# 02_CPU.net
KiCad netlist of a schematic drawn in Altium Designer
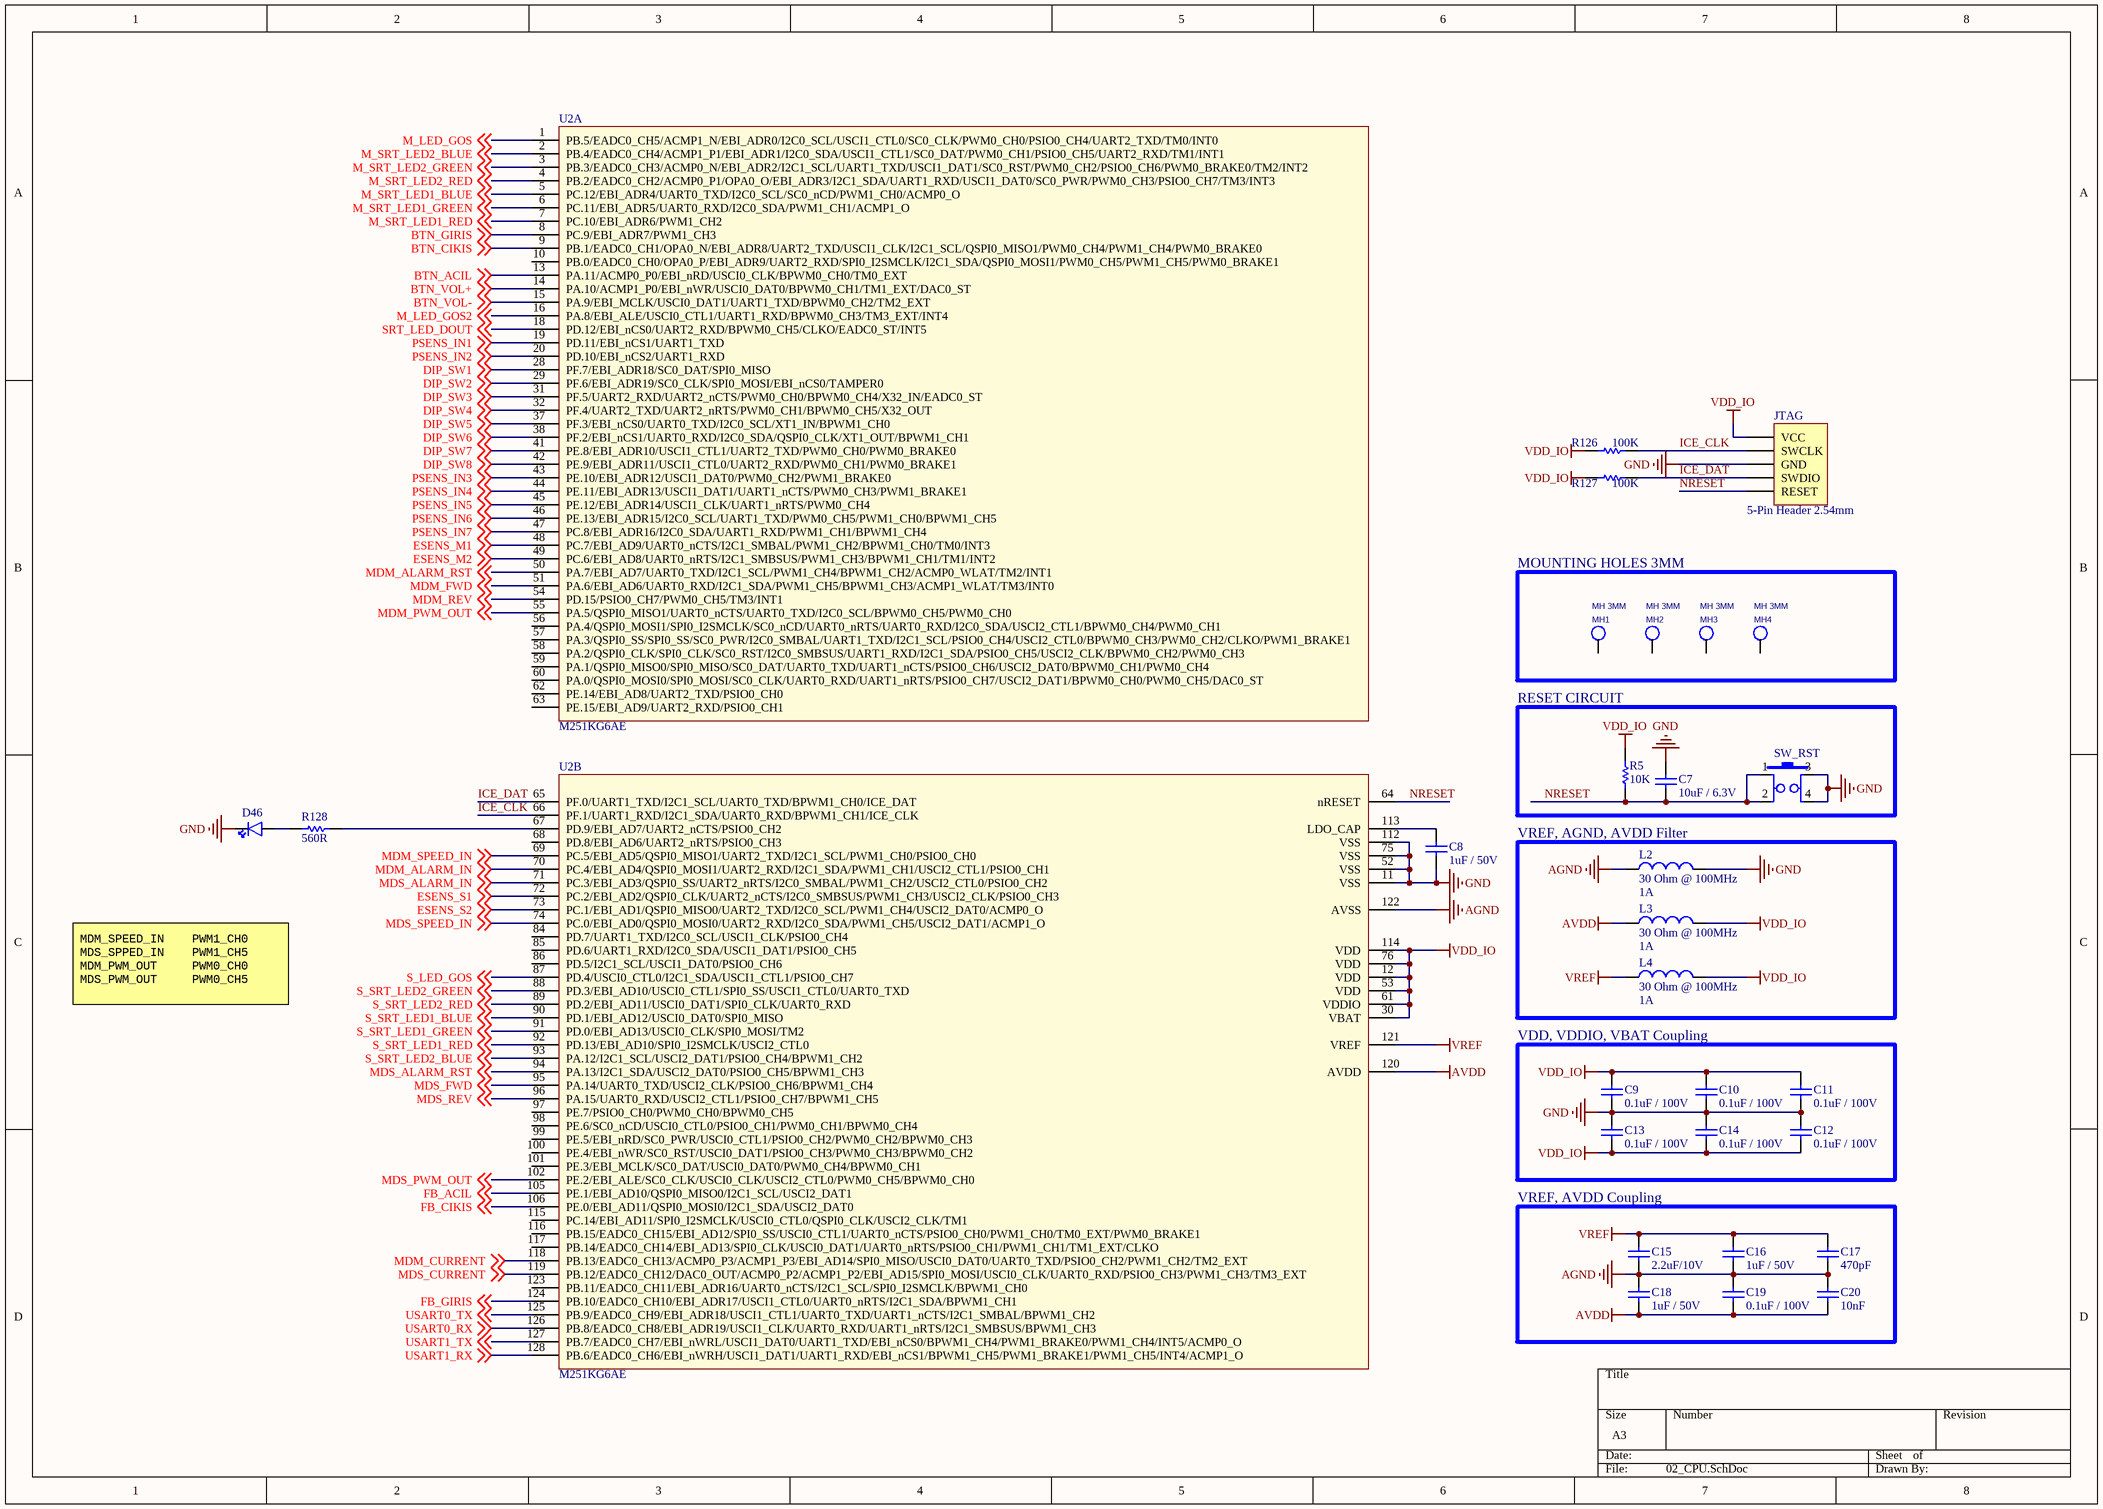
[diagram p0: 02_CPU.SchDoc]

(export (version "E")
  (design (tool "Eeschema 10.0.6"))
  (components
    (comp (ref "C7")
      (value "10uF / 6.3V")
      (footprint "603C")
      (description "10µF ±20% 6.3V Ceramic Capacitor X5R 0603 (1608 Metric)")
      (fields
        (field (name "DIGI-KEY PART NUMBER") "1276-1119-1-ND")
        (field (name "MANUFACTURER") "Samsung Electro-Mechanics")
      )
      (libsource (lib "FKDZ_Altium_Lib") (part "CAP_CER 10UF 6.3V X5R 0603"))
    )
    (comp (ref "C8")
      (value "1uF / 50V")
      (footprint "603C")
      (description "1µF ±10% 50V Ceramic Capacitor X5R 0603 (1608 Metric)")
      (fields
        (field (name "DIGI-KEY PART NUMBER") "1276-1860-2-ND")
        (field (name "MANUFACTURER") "Samsung Electro-Mechanics")
      )
      (libsource (lib "FKDZ_Altium_Lib") (part "CAP CER 1UF 50V X5R 0603"))
    )
    (comp (ref "C9")
      (value "0.1uF / 100V")
      (footprint "603C")
      (description "0.1 µF ±10% 100V Ceramic Capacitor X7R 0603 (1608 Metric)")
      (fields
        (field (name "DIGI-KEY PART NUMBER") "2679-C0603X7R101-104KNPTR-ND")
        (field (name "MANUFACTURER") "Venkel")
      )
      (libsource (lib "FKDZ_Altium_Lib") (part "CAP CER 0.1UF 100V X7R 0603"))
    )
    (comp (ref "C10")
      (value "0.1uF / 100V")
      (footprint "603C")
      (description "0.1 µF ±10% 100V Ceramic Capacitor X7R 0603 (1608 Metric)")
      (fields
        (field (name "DIGI-KEY PART NUMBER") "2679-C0603X7R101-104KNPTR-ND")
        (field (name "MANUFACTURER") "Venkel")
      )
      (libsource (lib "FKDZ_Altium_Lib") (part "CAP CER 0.1UF 100V X7R 0603"))
    )
    (comp (ref "C11")
      (value "0.1uF / 100V")
      (footprint "603C")
      (description "0.1 µF ±10% 100V Ceramic Capacitor X7R 0603 (1608 Metric)")
      (fields
        (field (name "DIGI-KEY PART NUMBER") "2679-C0603X7R101-104KNPTR-ND")
        (field (name "MANUFACTURER") "Venkel")
      )
      (libsource (lib "FKDZ_Altium_Lib") (part "CAP CER 0.1UF 100V X7R 0603"))
    )
    (comp (ref "C12")
      (value "0.1uF / 100V")
      (footprint "603C")
      (description "0.1 µF ±10% 100V Ceramic Capacitor X7R 0603 (1608 Metric)")
      (fields
        (field (name "DIGI-KEY PART NUMBER") "2679-C0603X7R101-104KNPTR-ND")
        (field (name "MANUFACTURER") "Venkel")
      )
      (libsource (lib "FKDZ_Altium_Lib") (part "CAP CER 0.1UF 100V X7R 0603"))
    )
    (comp (ref "C13")
      (value "0.1uF / 100V")
      (footprint "603C")
      (description "0.1 µF ±10% 100V Ceramic Capacitor X7R 0603 (1608 Metric)")
      (fields
        (field (name "DIGI-KEY PART NUMBER") "2679-C0603X7R101-104KNPTR-ND")
        (field (name "MANUFACTURER") "Venkel")
      )
      (libsource (lib "FKDZ_Altium_Lib") (part "CAP CER 0.1UF 100V X7R 0603"))
    )
    (comp (ref "C14")
      (value "0.1uF / 100V")
      (footprint "603C")
      (description "0.1 µF ±10% 100V Ceramic Capacitor X7R 0603 (1608 Metric)")
      (fields
        (field (name "DIGI-KEY PART NUMBER") "2679-C0603X7R101-104KNPTR-ND")
        (field (name "MANUFACTURER") "Venkel")
      )
      (libsource (lib "FKDZ_Altium_Lib") (part "CAP CER 0.1UF 100V X7R 0603"))
    )
    (comp (ref "C15")
      (value "2.2uF/10V")
      (footprint "603C")
      (description "2.2 µF ±10% 10V Ceramic Capacitor X5R 0603 (1608 Metric)")
      (fields
        (field (name "DIGI-KEY PART NUMBER") "2571-GMC10X5R225K10NTTR-ND")
        (field (name "MANUFACTURER") "CAL-CHIP ELECTRONICS, INC.")
      )
      (libsource (lib "FKDZ_Altium_Lib") (part "CAP CER 2.2UF 10V X5R 0603"))
    )
    (comp (ref "C16")
      (value "1uF / 50V")
      (footprint "603C")
      (description "1µF ±10% 50V Ceramic Capacitor X5R 0603 (1608 Metric)")
      (fields
        (field (name "DIGI-KEY PART NUMBER") "1276-1860-2-ND")
        (field (name "MANUFACTURER") "Samsung Electro-Mechanics")
      )
      (libsource (lib "FKDZ_Altium_Lib") (part "CAP CER 1UF 50V X5R 0603"))
    )
    (comp (ref "C17")
      (value "470pF")
      (footprint "603C")
      (description "470pF ±5% 50V Ceramic Capacitor C0G, NP0 0603 (1608 Metric)")
      (fields
        (field (name "DIGI-KEY PART NUMBER") "1276-1168-2-ND")
        (field (name "MANUFACTURER") "Samsung Electro-Mechanics America, Inc.")
      )
      (libsource (lib "FKDZ_Altium_Lib") (part "CAP_CER_470pF_50V_%5_C0G_NP0_ 0603"))
    )
    (comp (ref "C18")
      (value "1uF / 50V")
      (footprint "603C")
      (description "1µF ±10% 50V Ceramic Capacitor X5R 0603 (1608 Metric)")
      (fields
        (field (name "DIGI-KEY PART NUMBER") "1276-1860-2-ND")
        (field (name "MANUFACTURER") "Samsung Electro-Mechanics")
      )
      (libsource (lib "FKDZ_Altium_Lib") (part "CAP CER 1UF 50V X5R 0603"))
    )
    (comp (ref "C19")
      (value "0.1uF / 100V")
      (footprint "603C")
      (description "0.1 µF ±10% 100V Ceramic Capacitor X7R 0603 (1608 Metric)")
      (fields
        (field (name "DIGI-KEY PART NUMBER") "2679-C0603X7R101-104KNPTR-ND")
        (field (name "MANUFACTURER") "Venkel")
      )
      (libsource (lib "FKDZ_Altium_Lib") (part "CAP CER 0.1UF 100V X7R 0603"))
    )
    (comp (ref "C20")
      (value "10nF")
      (footprint "603C")
      (description "10nF ±5% 50V Ceramic Capacitor X7R 0603 (1608 Metric)")
      (fields (field (name "DIGI-KEY PART NUMBER") "311-1778-2-ND") (field (name "MANUFACTURER") "Yageo"))
      (libsource (lib "FKDZ_Altium_Lib") (part "CAP_CER_10nF_50V_%5_ X7R_ 0603"))
    )
    (comp (ref "D46")
      (value "led_green")
      (footprint "805LED")
      (description "LED 2X1.2MM 570NM GN WTR CLR SMD")
      (fields (field (name "DIGI-KEY PART NUMBER") "754-1127-1-ND"))
      (libsource (lib "FKDZ_Altium_Lib") (part "LED_GREEN_0805"))
    )
    (comp (ref "JTAG")
      (value "5-Pin Header 2.54mm")
      (footprint "HDR1X5")
      (description "STM JTAG Header, 5-Pin")
      (libsource (lib "FKDZ_Altium_Lib") (part "STM_JTAG"))
    )
    (comp (ref "L2")
      (value "30 Ohm @ 100MHz")
      (footprint "603L")
      (description "30 Ohms @ 100 MHz 1 Power Line Ferrite Bead 0603 (1608 Metric) 1A 50mOhm")
      (fields
        (field (name "DIGI-KEY PART NUMBER") "490-1035-1-ND")
        (field (name "MANUFACTURER") "Murata Electronics")
        (field (name "IMPEDANCE AT FREQUENCY") "30 Ohm @ 100MHz")
        (field (name "CURRENT RATING (MAX)") "1A")
      )
      (libsource (lib "FKDZ_Altium_Lib") (part "FERRITE BEAD 30 OHM 0603 1LN"))
    )
    (comp (ref "L3")
      (value "30 Ohm @ 100MHz")
      (footprint "603L")
      (description "30 Ohms @ 100 MHz 1 Power Line Ferrite Bead 0603 (1608 Metric) 1A 50mOhm")
      (fields
        (field (name "DIGI-KEY PART NUMBER") "490-1035-1-ND")
        (field (name "MANUFACTURER") "Murata Electronics")
        (field (name "IMPEDANCE AT FREQUENCY") "30 Ohm @ 100MHz")
        (field (name "CURRENT RATING (MAX)") "1A")
      )
      (libsource (lib "FKDZ_Altium_Lib") (part "FERRITE BEAD 30 OHM 0603 1LN"))
    )
    (comp (ref "L4")
      (value "30 Ohm @ 100MHz")
      (footprint "603L")
      (description "30 Ohms @ 100 MHz 1 Power Line Ferrite Bead 0603 (1608 Metric) 1A 50mOhm")
      (fields
        (field (name "DIGI-KEY PART NUMBER") "490-1035-1-ND")
        (field (name "MANUFACTURER") "Murata Electronics")
        (field (name "IMPEDANCE AT FREQUENCY") "30 Ohm @ 100MHz")
        (field (name "CURRENT RATING (MAX)") "1A")
      )
      (libsource (lib "FKDZ_Altium_Lib") (part "FERRITE BEAD 30 OHM 0603 1LN"))
    )
    (comp (ref "MH1")
      (value "MH 3MM")
      (footprint "MH 3.0MM HOLE 5MM PAD")
      (description "Mountin hole, NPTH Drill 3mm")
      (libsource (lib "FKDZ_Altium_Lib") (part "MH 3MMHOLE_5MMPAD"))
    )
    (comp (ref "MH2")
      (value "MH 3MM")
      (footprint "MH 3.0MM HOLE 5MM PAD")
      (description "Mountin hole, NPTH Drill 3mm")
      (libsource (lib "FKDZ_Altium_Lib") (part "MH 3MMHOLE_5MMPAD"))
    )
    (comp (ref "MH3")
      (value "MH 3MM")
      (footprint "MH 3.0MM HOLE 5MM PAD")
      (description "Mountin hole, NPTH Drill 3mm")
      (libsource (lib "FKDZ_Altium_Lib") (part "MH 3MMHOLE_5MMPAD"))
    )
    (comp (ref "MH4")
      (value "MH 3MM")
      (footprint "MH 3.0MM HOLE 5MM PAD")
      (description "Mountin hole, NPTH Drill 3mm")
      (libsource (lib "FKDZ_Altium_Lib") (part "MH 3MMHOLE_5MMPAD"))
    )
    (comp (ref "R5")
      (value "10K")
      (footprint "603R")
      (description "10 kOhms ±5% 0.1W, 1/10W Chip Resistor 0603 (1608 Metric) Moisture Resistant Thick Film")
      (fields (field (name "DIGI-KEY PART NUMBER") "311-10KGRTR-ND") (field (name "MANUFACTURER") "Yageo"))
      (libsource (lib "FKDZ_Altium_Lib") (part "RES_10K_OHM_%5_0.1W_0603"))
    )
    (comp (ref "R126")
      (value "100K")
      (footprint "603R")
      (description "100 kOhms ±1% 0.1W, 1/10W Chip Resistor 0603 (1608 Metric)  Thick Film")
      (fields
        (field (name "DIGI-KEY PART NUMBER") "A106046TR-ND")
        (field (name "MANUFACTURER") "TE Connectivity Passive Product")
      )
      (libsource (lib "FKDZ_Altium_Lib") (part "RES_100K OHM 1% 1/10W 0603"))
    )
    (comp (ref "R127")
      (value "100K")
      (footprint "603R")
      (description "100 kOhms ±1% 0.1W, 1/10W Chip Resistor 0603 (1608 Metric)  Thick Film")
      (fields
        (field (name "DIGI-KEY PART NUMBER") "A106046TR-ND")
        (field (name "MANUFACTURER") "TE Connectivity Passive Product")
      )
      (libsource (lib "FKDZ_Altium_Lib") (part "RES_100K OHM 1% 1/10W 0603"))
    )
    (comp (ref "R128")
      (value "560R")
      (footprint "603R")
      (description "560 Ohms ±5% 0.1W, 1/10W Chip Resistor 0603 (1608 Metric) Moisture Resistant Thick Film")
      (fields (field (name "DIGI-KEY PART NUMBER") "311-560GRCT-ND") (field (name "MANUFACTURER") "Yageo"))
      (libsource (lib "FKDZ_Altium_Lib") (part "RES_560_OHM_%5_0.1W_0603"))
    )
    (comp (ref "SW_RST")
      (value "switch tactile")
      (footprint "SW_TACTILE_6X6mm SMT")
      (description "Tactile Switch SPST-NO Top Actuated Surface Mount")
      (fields (field (name "DIGI-KEY PART NUMBER") "CKN9112TR-ND"))
      (libsource (lib "FKDZ_Altium_Lib") (part "SW_TACTILE_6x6x4.3mm SMT"))
    )
    (comp (ref "U2")
      (value "M251KG6AE")
      (footprint "TSQFP40P1600X1600X160-128N")
      (description "ARM® Cortex®-M23 series Microcontroller IC 32-Bit 48MHz 256KB (256K x 8) FLASH 128-LQFP (14x14)")
      (fields
        (field (name "DIGI-KEY PART NUMBER") "https://www.ozdisan.com/integrated-circuits-ics/embedded-ics/microcontrollers/M251KG6AE")
      )
      (libsource (lib "") (part "IC MCU 32BIT 256KB FLASH 32KB RAM 128LQFP M251KG6AE_1"))
    )
  )
  (nets
    (net (code "1") (name "/ICE_CLK") (class "Default")
      (node (ref "JTAG") (pin "2") (pinfunction "SWCLK_2") (pintype "passive"))
      (node (ref "R126") (pin "2") (pinfunction "2_2") (pintype "passive"))
      (node (ref "U2") (pin "66") (pinfunction "PF.1/UART1_RXD/I2C1_SDA/UART0_RXD/BPWM1_CH1/ICE_CLK_66") (pintype "passive"))
    )
    (net (code "2") (name "/ICE_DAT") (class "Default")
      (node (ref "JTAG") (pin "4") (pinfunction "SWDIO_4") (pintype "passive"))
      (node (ref "R127") (pin "2") (pinfunction "2_2") (pintype "passive"))
      (node (ref "U2") (pin "65") (pinfunction "PF.0/UART1_TXD/I2C1_SCL/UART0_TXD/BPWM1_CH0/ICE_DAT_65") (pintype "passive"))
    )
    (net (code "3") (name "/NRESET") (class "Default")
      (node (ref "C7") (pin "2") (pinfunction "2_2") (pintype "passive"))
      (node (ref "JTAG") (pin "5") (pinfunction "RESET_5") (pintype "passive"))
      (node (ref "R5") (pin "1") (pinfunction "1_1") (pintype "passive"))
      (node (ref "SW_RST") (pin "1") (pinfunction "1_1") (pintype "passive"))
      (node (ref "SW_RST") (pin "2") (pinfunction "2_2") (pintype "passive"))
      (node (ref "U2") (pin "64") (pinfunction "nRESET_64") (pintype "passive"))
    )
    (net (code "4") (name "AGND") (class "Default")
      (node (ref "C15") (pin "1") (pinfunction "1_1") (pintype "passive"))
      (node (ref "C16") (pin "1") (pinfunction "1_1") (pintype "passive"))
      (node (ref "C17") (pin "1") (pinfunction "1_1") (pintype "passive"))
      (node (ref "C18") (pin "2") (pinfunction "2_2") (pintype "passive"))
      (node (ref "C19") (pin "2") (pinfunction "2_2") (pintype "passive"))
      (node (ref "C20") (pin "2") (pinfunction "2_2") (pintype "passive"))
      (node (ref "L2") (pin "1") (pinfunction "1_1") (pintype "passive"))
      (node (ref "U2") (pin "122") (pinfunction "AVSS_122") (pintype "passive"))
    )
    (net (code "5") (name "AVDD") (class "Default")
      (node (ref "C18") (pin "1") (pinfunction "1_1") (pintype "passive"))
      (node (ref "C19") (pin "1") (pinfunction "1_1") (pintype "passive"))
      (node (ref "C20") (pin "1") (pinfunction "1_1") (pintype "passive"))
      (node (ref "L3") (pin "1") (pinfunction "1_1") (pintype "passive"))
      (node (ref "U2") (pin "120") (pinfunction "AVDD_120") (pintype "passive"))
    )
    (net (code "6") (name "BTN_ACIL") (class "Default")
      (node (ref "U2") (pin "13") (pinfunction "PA.11/ACMP0_P0/EBI_nRD/USCI0_CLK/BPWM0_CH0/TM0_EXT_13") (pintype "passive"))
    )
    (net (code "7") (name "BTN_CIKIS") (class "Default")
      (node (ref "U2") (pin "9") (pinfunction "PB.1/EADC0_CH1/OPA0_N/EBI_ADR8/UART2_TXD/USCI1_CLK/I2C1_SCL/QSPI0_MISO1/PWM0_CH4/PWM1_CH4/PWM0_BRAKE0_9") (pintype "passive"))
    )
    (net (code "8") (name "BTN_GIRIS") (class "Default")
      (node (ref "U2") (pin "8") (pinfunction "PC.9/EBI_ADR7/PWM1_CH3_8") (pintype "passive"))
    )
    (net (code "9") (name "BTN_VOL+") (class "Default")
      (node (ref "U2") (pin "14") (pinfunction "PA.10/ACMP1_P0/EBI_nWR/USCI0_DAT0/BPWM0_CH1/TM1_EXT/DAC0_ST_14") (pintype "passive"))
    )
    (net (code "10") (name "BTN_VOL-") (class "Default")
      (node (ref "U2") (pin "15") (pinfunction "PA.9/EBI_MCLK/USCI0_DAT1/UART1_TXD/BPWM0_CH2/TM2_EXT_15") (pintype "passive"))
    )
    (net (code "11") (name "DIP_SW1") (class "Default")
      (node (ref "U2") (pin "28") (pinfunction "PF.7/EBI_ADR18/SC0_DAT/SPI0_MISO_28") (pintype "passive"))
    )
    (net (code "12") (name "DIP_SW2") (class "Default")
      (node (ref "U2") (pin "29") (pinfunction "PF.6/EBI_ADR19/SC0_CLK/SPI0_MOSI/EBI_nCS0/TAMPER0_29") (pintype "passive"))
    )
    (net (code "13") (name "DIP_SW3") (class "Default")
      (node (ref "U2") (pin "31") (pinfunction "PF.5/UART2_RXD/UART2_nCTS/PWM0_CH0/BPWM0_CH4/X32_IN/EADC0_ST_31") (pintype "passive"))
    )
    (net (code "14") (name "DIP_SW4") (class "Default")
      (node (ref "U2") (pin "32") (pinfunction "PF.4/UART2_TXD/UART2_nRTS/PWM0_CH1/BPWM0_CH5/X32_OUT_32") (pintype "passive"))
    )
    (net (code "15") (name "DIP_SW5") (class "Default")
      (node (ref "U2") (pin "37") (pinfunction "PF.3/EBI_nCS0/UART0_TXD/I2C0_SCL/XT1_IN/BPWM1_CH0_37") (pintype "passive"))
    )
    (net (code "16") (name "DIP_SW6") (class "Default")
      (node (ref "U2") (pin "38") (pinfunction "PF.2/EBI_nCS1/UART0_RXD/I2C0_SDA/QSPI0_CLK/XT1_OUT/BPWM1_CH1_38") (pintype "passive"))
    )
    (net (code "17") (name "DIP_SW7") (class "Default")
      (node (ref "U2") (pin "41") (pinfunction "PE.8/EBI_ADR10/USCI1_CTL1/UART2_TXD/PWM0_CH0/PWM0_BRAKE0_41") (pintype "passive"))
    )
    (net (code "18") (name "DIP_SW8") (class "Default")
      (node (ref "U2") (pin "42") (pinfunction "PE.9/EBI_ADR11/USCI1_CTL0/UART2_RXD/PWM0_CH1/PWM0_BRAKE1_42") (pintype "passive"))
    )
    (net (code "19") (name "ESENS_M1") (class "Default")
      (node (ref "U2") (pin "48") (pinfunction "PC.7/EBI_AD9/UART0_nCTS/I2C1_SMBAL/PWM1_CH2/BPWM1_CH0/TM0/INT3_48") (pintype "passive"))
    )
    (net (code "20") (name "ESENS_M2") (class "Default")
      (node (ref "U2") (pin "49") (pinfunction "PC.6/EBI_AD8/UART0_nRTS/I2C1_SMBSUS/PWM1_CH3/BPWM1_CH1/TM1/INT2_49") (pintype "passive"))
    )
    (net (code "21") (name "ESENS_S1") (class "Default")
      (node (ref "U2") (pin "72") (pinfunction "PC.2/EBI_AD2/QSPI0_CLK/UART2_nCTS/I2C0_SMBSUS/PWM1_CH3/USCI2_CLK/PSIO0_CH3_72") (pintype "passive"))
    )
    (net (code "22") (name "ESENS_S2") (class "Default")
      (node (ref "U2") (pin "73") (pinfunction "PC.1/EBI_AD1/QSPI0_MISO0/UART2_TXD/I2C0_SCL/PWM1_CH4/USCI2_DAT0/ACMP0_O_73") (pintype "passive"))
    )
    (net (code "23") (name "FB_ACIL") (class "Default")
      (node (ref "U2") (pin "105") (pinfunction "PE.1/EBI_AD10/QSPI0_MISO0/I2C1_SCL/USCI2_DAT1_105") (pintype "passive"))
    )
    (net (code "24") (name "FB_CIKIS") (class "Default")
      (node (ref "U2") (pin "106") (pinfunction "PE.0/EBI_AD11/QSPI0_MOSI0/I2C1_SDA/USCI2_DAT0_106") (pintype "passive"))
    )
    (net (code "25") (name "FB_GIRIS") (class "Default")
      (node (ref "U2") (pin "124") (pinfunction "PB.10/EADC0_CH10/EBI_ADR17/USCI1_CTL0/UART0_nRTS/I2C1_SDA/BPWM1_CH1_124") (pintype "passive"))
    )
    (net (code "26") (name "GND") (class "Default")
      (node (ref "C10") (pin "1") (pinfunction "1_1") (pintype "passive"))
      (node (ref "C11") (pin "1") (pinfunction "1_1") (pintype "passive"))
      (node (ref "C12") (pin "1") (pinfunction "1_1") (pintype "passive"))
      (node (ref "C13") (pin "2") (pinfunction "2_2") (pintype "passive"))
      (node (ref "C14") (pin "2") (pinfunction "2_2") (pintype "passive"))
      (node (ref "C7") (pin "1") (pinfunction "1_1") (pintype "passive"))
      (node (ref "C8") (pin "1") (pinfunction "1_1") (pintype "passive"))
      (node (ref "C9") (pin "1") (pinfunction "1_1") (pintype "passive"))
      (node (ref "D46") (pin "2") (pinfunction "K_2") (pintype "passive"))
      (node (ref "JTAG") (pin "3") (pinfunction "GND_3") (pintype "power_in"))
      (node (ref "L2") (pin "2") (pinfunction "2_2") (pintype "passive"))
      (node (ref "SW_RST") (pin "3") (pinfunction "3_3") (pintype "passive"))
      (node (ref "SW_RST") (pin "4") (pinfunction "4_4") (pintype "passive"))
      (node (ref "U2") (pin "11") (pinfunction "VSS_11") (pintype "passive"))
      (node (ref "U2") (pin "112") (pinfunction "VSS_112") (pintype "passive"))
      (node (ref "U2") (pin "52") (pinfunction "VSS_52") (pintype "passive"))
      (node (ref "U2") (pin "75") (pinfunction "VSS_75") (pintype "passive"))
    )
    (net (code "27") (name "MDM_ALARM_IN") (class "Default")
      (node (ref "U2") (pin "70") (pinfunction "PC.4/EBI_AD4/QSPI0_MOSI1/UART2_RXD/I2C1_SDA/PWM1_CH1/USCI2_CTL1/PSIO0_CH1_70") (pintype "passive"))
    )
    (net (code "28") (name "MDM_ALARM_RST") (class "Default")
      (node (ref "U2") (pin "50") (pinfunction "PA.7/EBI_AD7/UART0_TXD/I2C1_SCL/PWM1_CH4/BPWM1_CH2/ACMP0_WLAT/TM2/INT1_50") (pintype "passive"))
    )
    (net (code "29") (name "MDM_CURRENT") (class "Default")
      (node (ref "U2") (pin "118") (pinfunction "PB.13/EADC0_CH13/ACMP0_P3/ACMP1_P3/EBI_AD14/SPI0_MISO/USCI0_DAT0/UART0_TXD/PSIO0_CH2/PWM1_CH2/TM2_EXT_118") (pintype "passive"))
    )
    (net (code "30") (name "MDM_FWD") (class "Default")
      (node (ref "U2") (pin "51") (pinfunction "PA.6/EBI_AD6/UART0_RXD/I2C1_SDA/PWM1_CH5/BPWM1_CH3/ACMP1_WLAT/TM3/INT0_51") (pintype "passive"))
    )
    (net (code "31") (name "MDM_PWM_OUT") (class "Default")
      (node (ref "U2") (pin "55") (pinfunction "PA.5/QSPI0_MISO1/UART0_nCTS/UART0_TXD/I2C0_SCL/BPWM0_CH5/PWM0_CH0_55") (pintype "passive"))
    )
    (net (code "32") (name "MDM_REV") (class "Default")
      (node (ref "U2") (pin "54") (pinfunction "PD.15/PSIO0_CH7/PWM0_CH5/TM3/INT1_54") (pintype "passive"))
    )
    (net (code "33") (name "MDM_SPEED_IN") (class "Default")
      (node (ref "U2") (pin "69") (pinfunction "PC.5/EBI_AD5/QSPI0_MISO1/UART2_TXD/I2C1_SCL/PWM1_CH0/PSIO0_CH0_69") (pintype "passive"))
    )
    (net (code "34") (name "MDS_ALARM_IN") (class "Default")
      (node (ref "U2") (pin "71") (pinfunction "PC.3/EBI_AD3/QSPI0_SS/UART2_nRTS/I2C0_SMBAL/PWM1_CH2/USCI2_CTL0/PSIO0_CH2_71") (pintype "passive"))
    )
    (net (code "35") (name "MDS_ALARM_RST") (class "Default")
      (node (ref "U2") (pin "94") (pinfunction "PA.13/I2C1_SDA/USCI2_DAT0/PSIO0_CH5/BPWM1_CH3_94") (pintype "passive"))
    )
    (net (code "36") (name "MDS_CURRENT") (class "Default")
      (node (ref "U2") (pin "119") (pinfunction "PB.12/EADC0_CH12/DAC0_OUT/ACMP0_P2/ACMP1_P2/EBI_AD15/SPI0_MOSI/USCI0_CLK/UART0_RXD/PSIO0_CH3/PWM1_CH3/TM3_EXT_119") (pintype "passive"))
    )
    (net (code "37") (name "MDS_FWD") (class "Default")
      (node (ref "U2") (pin "95") (pinfunction "PA.14/UART0_TXD/USCI2_CLK/PSIO0_CH6/BPWM1_CH4_95") (pintype "passive"))
    )
    (net (code "38") (name "MDS_PWM_OUT") (class "Default")
      (node (ref "U2") (pin "102") (pinfunction "PE.2/EBI_ALE/SC0_CLK/USCI0_CLK/USCI2_CTL0/PWM0_CH5/BPWM0_CH0_102") (pintype "passive"))
    )
    (net (code "39") (name "MDS_REV") (class "Default")
      (node (ref "U2") (pin "96") (pinfunction "PA.15/UART0_RXD/USCI2_CTL1/PSIO0_CH7/BPWM1_CH5_96") (pintype "passive"))
    )
    (net (code "40") (name "MDS_SPEED_IN") (class "Default")
      (node (ref "U2") (pin "74") (pinfunction "PC.0/EBI_AD0/QSPI0_MOSI0/UART2_RXD/I2C0_SDA/PWM1_CH5/USCI2_DAT1/ACMP1_O_74") (pintype "passive"))
    )
    (net (code "41") (name "M_LED_GOS") (class "Default")
      (node (ref "U2") (pin "1") (pinfunction "PB.5/EADC0_CH5/ACMP1_N/EBI_ADR0/I2C0_SCL/USCI1_CTL0/SC0_CLK/PWM0_CH0/PSIO0_CH4/UART2_TXD/TM0/INT0_1") (pintype "passive"))
    )
    (net (code "42") (name "M_LED_GOS2") (class "Default")
      (node (ref "U2") (pin "16") (pinfunction "PA.8/EBI_ALE/USCI0_CTL1/UART1_RXD/BPWM0_CH3/TM3_EXT/INT4_16") (pintype "passive"))
    )
    (net (code "43") (name "M_SRT_LED1_BLUE") (class "Default")
      (node (ref "U2") (pin "5") (pinfunction "PC.12/EBI_ADR4/UART0_TXD/I2C0_SCL/SC0_nCD/PWM1_CH0/ACMP0_O_5") (pintype "passive"))
    )
    (net (code "44") (name "M_SRT_LED1_GREEN") (class "Default")
      (node (ref "U2") (pin "6") (pinfunction "PC.11/EBI_ADR5/UART0_RXD/I2C0_SDA/PWM1_CH1/ACMP1_O_6") (pintype "passive"))
    )
    (net (code "45") (name "M_SRT_LED1_RED") (class "Default")
      (node (ref "U2") (pin "7") (pinfunction "PC.10/EBI_ADR6/PWM1_CH2_7") (pintype "passive"))
    )
    (net (code "46") (name "M_SRT_LED2_BLUE") (class "Default")
      (node (ref "U2") (pin "2") (pinfunction "PB.4/EADC0_CH4/ACMP1_P1/EBI_ADR1/I2C0_SDA/USCI1_CTL1/SC0_DAT/PWM0_CH1/PSIO0_CH5/UART2_RXD/TM1/INT1_2") (pintype "passive"))
    )
    (net (code "47") (name "M_SRT_LED2_GREEN") (class "Default")
      (node (ref "U2") (pin "3") (pinfunction "PB.3/EADC0_CH3/ACMP0_N/EBI_ADR2/I2C1_SCL/UART1_TXD/USCI1_DAT1/SC0_RST/PWM0_CH2/PSIO0_CH6/PWM0_BRAKE0/TM2/INT2_3") (pintype "passive"))
    )
    (net (code "48") (name "M_SRT_LED2_RED") (class "Default")
      (node (ref "U2") (pin "4") (pinfunction "PB.2/EADC0_CH2/ACMP0_P1/OPA0_O/EBI_ADR3/I2C1_SDA/UART1_RXD/USCI1_DAT0/SC0_PWR/PWM0_CH3/PSIO0_CH7/TM3/INT3_4") (pintype "passive"))
    )
    (net (code "49") (name "Net-(D46-A)") (class "Default")
      (node (ref "D46") (pin "1") (pinfunction "A_1") (pintype "passive"))
      (node (ref "R128") (pin "2") (pinfunction "2_2") (pintype "passive"))
    )
    (net (code "50") (name "Net-(U2B-LDO_CAP)") (class "Default")
      (node (ref "C8") (pin "2") (pinfunction "2_2") (pintype "passive"))
      (node (ref "U2") (pin "113") (pinfunction "LDO_CAP_113") (pintype "passive"))
    )
    (net (code "51") (name "Net-(U2B-PD.9{slash}EBI_AD7{slash}UART2_nCTS{slash}PSIO0_CH2)") (class "Default")
      (node (ref "R128") (pin "1") (pinfunction "1_1") (pintype "passive"))
      (node (ref "U2") (pin "67") (pinfunction "PD.9/EBI_AD7/UART2_nCTS/PSIO0_CH2_67") (pintype "passive"))
    )
    (net (code "52") (name "PSENS_IN1") (class "Default")
      (node (ref "U2") (pin "19") (pinfunction "PD.11/EBI_nCS1/UART1_TXD_19") (pintype "passive"))
    )
    (net (code "53") (name "PSENS_IN2") (class "Default")
      (node (ref "U2") (pin "20") (pinfunction "PD.10/EBI_nCS2/UART1_RXD_20") (pintype "passive"))
    )
    (net (code "54") (name "PSENS_IN3") (class "Default")
      (node (ref "U2") (pin "43") (pinfunction "PE.10/EBI_ADR12/USCI1_DAT0/PWM0_CH2/PWM1_BRAKE0_43") (pintype "passive"))
    )
    (net (code "55") (name "PSENS_IN4") (class "Default")
      (node (ref "U2") (pin "44") (pinfunction "PE.11/EBI_ADR13/USCI1_DAT1/UART1_nCTS/PWM0_CH3/PWM1_BRAKE1_44") (pintype "passive"))
    )
    (net (code "56") (name "PSENS_IN5") (class "Default")
      (node (ref "U2") (pin "45") (pinfunction "PE.12/EBI_ADR14/USCI1_CLK/UART1_nRTS/PWM0_CH4_45") (pintype "passive"))
    )
    (net (code "57") (name "PSENS_IN6") (class "Default")
      (node (ref "U2") (pin "46") (pinfunction "PE.13/EBI_ADR15/I2C0_SCL/UART1_TXD/PWM0_CH5/PWM1_CH0/BPWM1_CH5_46") (pintype "passive"))
    )
    (net (code "58") (name "PSENS_IN7") (class "Default")
      (node (ref "U2") (pin "47") (pinfunction "PC.8/EBI_ADR16/I2C0_SDA/UART1_RXD/PWM1_CH1/BPWM1_CH4_47") (pintype "passive"))
    )
    (net (code "59") (name "SRT_LED_DOUT") (class "Default")
      (node (ref "U2") (pin "18") (pinfunction "PD.12/EBI_nCS0/UART2_RXD/BPWM0_CH5/CLKO/EADC0_ST/INT5_18") (pintype "passive"))
    )
    (net (code "60") (name "S_LED_GOS") (class "Default")
      (node (ref "U2") (pin "87") (pinfunction "PD.4/USCI0_CTL0/I2C1_SDA/USCI1_CTL1/PSIO0_CH7_87") (pintype "passive"))
    )
    (net (code "61") (name "S_SRT_LED1_BLUE") (class "Default")
      (node (ref "U2") (pin "90") (pinfunction "PD.1/EBI_AD12/USCI0_DAT0/SPI0_MISO_90") (pintype "passive"))
    )
    (net (code "62") (name "S_SRT_LED1_GREEN") (class "Default")
      (node (ref "U2") (pin "91") (pinfunction "PD.0/EBI_AD13/USCI0_CLK/SPI0_MOSI/TM2_91") (pintype "passive"))
    )
    (net (code "63") (name "S_SRT_LED1_RED") (class "Default")
      (node (ref "U2") (pin "92") (pinfunction "PD.13/EBI_AD10/SPI0_I2SMCLK/USCI2_CTL0_92") (pintype "passive"))
    )
    (net (code "64") (name "S_SRT_LED2_BLUE") (class "Default")
      (node (ref "U2") (pin "93") (pinfunction "PA.12/I2C1_SCL/USCI2_DAT1/PSIO0_CH4/BPWM1_CH2_93") (pintype "passive"))
    )
    (net (code "65") (name "S_SRT_LED2_GREEN") (class "Default")
      (node (ref "U2") (pin "88") (pinfunction "PD.3/EBI_AD10/USCI0_CTL1/SPI0_SS/USCI1_CTL0/UART0_TXD_88") (pintype "passive"))
    )
    (net (code "66") (name "S_SRT_LED2_RED") (class "Default")
      (node (ref "U2") (pin "89") (pinfunction "PD.2/EBI_AD11/USCI0_DAT1/SPI0_CLK/UART0_RXD_89") (pintype "passive"))
    )
    (net (code "67") (name "USART0_RX") (class "Default")
      (node (ref "U2") (pin "126") (pinfunction "PB.8/EADC0_CH8/EBI_ADR19/USCI1_CLK/UART0_RXD/UART1_nRTS/I2C1_SMBSUS/BPWM1_CH3_126") (pintype "passive"))
    )
    (net (code "68") (name "USART0_TX") (class "Default")
      (node (ref "U2") (pin "125") (pinfunction "PB.9/EADC0_CH9/EBI_ADR18/USCI1_CTL1/UART0_TXD/UART1_nCTS/I2C1_SMBAL/BPWM1_CH2_125") (pintype "passive"))
    )
    (net (code "69") (name "USART1_RX") (class "Default")
      (node (ref "U2") (pin "128") (pinfunction "PB.6/EADC0_CH6/EBI_nWRH/USCI1_DAT1/UART1_RXD/EBI_nCS1/BPWM1_CH5/PWM1_BRAKE1/PWM1_CH5/INT4/ACMP1_O_128") (pintype "passive"))
    )
    (net (code "70") (name "USART1_TX") (class "Default")
      (node (ref "U2") (pin "127") (pinfunction "PB.7/EADC0_CH7/EBI_nWRL/USCI1_DAT0/UART1_TXD/EBI_nCS0/BPWM1_CH4/PWM1_BRAKE0/PWM1_CH4/INT5/ACMP0_O_127") (pintype "passive"))
    )
    (net (code "71") (name "VDD_IO") (class "Default")
      (node (ref "C10") (pin "2") (pinfunction "2_2") (pintype "passive"))
      (node (ref "C11") (pin "2") (pinfunction "2_2") (pintype "passive"))
      (node (ref "C12") (pin "2") (pinfunction "2_2") (pintype "passive"))
      (node (ref "C13") (pin "1") (pinfunction "1_1") (pintype "passive"))
      (node (ref "C14") (pin "1") (pinfunction "1_1") (pintype "passive"))
      (node (ref "C9") (pin "2") (pinfunction "2_2") (pintype "passive"))
      (node (ref "JTAG") (pin "1") (pinfunction "VCC_1") (pintype "power_in"))
      (node (ref "L3") (pin "2") (pinfunction "2_2") (pintype "passive"))
      (node (ref "L4") (pin "2") (pinfunction "2_2") (pintype "passive"))
      (node (ref "R126") (pin "1") (pinfunction "1_1") (pintype "passive"))
      (node (ref "R127") (pin "1") (pinfunction "1_1") (pintype "passive"))
      (node (ref "R5") (pin "2") (pinfunction "2_2") (pintype "passive"))
      (node (ref "U2") (pin "114") (pinfunction "VDD_114") (pintype "passive"))
      (node (ref "U2") (pin "12") (pinfunction "VDD_12") (pintype "passive"))
      (node (ref "U2") (pin "30") (pinfunction "VBAT_30") (pintype "passive"))
      (node (ref "U2") (pin "53") (pinfunction "VDD_53") (pintype "passive"))
      (node (ref "U2") (pin "61") (pinfunction "VDDIO_61") (pintype "passive"))
      (node (ref "U2") (pin "76") (pinfunction "VDD_76") (pintype "passive"))
    )
    (net (code "72") (name "VREF") (class "Default")
      (node (ref "C15") (pin "2") (pinfunction "2_2") (pintype "passive"))
      (node (ref "C16") (pin "2") (pinfunction "2_2") (pintype "passive"))
      (node (ref "C17") (pin "2") (pinfunction "2_2") (pintype "passive"))
      (node (ref "L4") (pin "1") (pinfunction "1_1") (pintype "passive"))
      (node (ref "U2") (pin "121") (pinfunction "VREF_121") (pintype "passive"))
    )
    (net (code "73") (name "unconnected-(MH1-Pad1)") (class "Default")
      (node (ref "MH1") (pin "1") (pinfunction "1_1") (pintype "passive"))
    )
    (net (code "74") (name "unconnected-(MH2-Pad1)") (class "Default")
      (node (ref "MH2") (pin "1") (pinfunction "1_1") (pintype "passive"))
    )
    (net (code "75") (name "unconnected-(MH3-Pad1)") (class "Default")
      (node (ref "MH3") (pin "1") (pinfunction "1_1") (pintype "passive"))
    )
    (net (code "76") (name "unconnected-(MH4-Pad1)") (class "Default")
      (node (ref "MH4") (pin "1") (pinfunction "1_1") (pintype "passive"))
    )
    (net (code "77") (name "unconnected-(U2A-PA.0{slash}QSPI0_MOSI0{slash}SPI0_MOSI{slash}SC0_CLK{slash}UART0_RXD{slash}UART1_nRTS{slash}PSIO0_CH7{slash}USCI2_DAT1{slash}BPWM0_CH0{slash}PWM0_CH5{slash}DAC0_ST-Pad60)") (class "Default")
      (node (ref "U2") (pin "60") (pinfunction "PA.0/QSPI0_MOSI0/SPI0_MOSI/SC0_CLK/UART0_RXD/UART1_nRTS/PSIO0_CH7/USCI2_DAT1/BPWM0_CH0/PWM0_CH5/DAC0_ST_60") (pintype "passive"))
    )
    (net (code "78") (name "unconnected-(U2A-PA.1{slash}QSPI0_MISO0{slash}SPI0_MISO{slash}SC0_DAT{slash}UART0_TXD{slash}UART1_nCTS{slash}PSIO0_CH6{slash}USCI2_DAT0{slash}BPWM0_CH1{slash}PWM0_CH4-Pad59)") (class "Default")
      (node (ref "U2") (pin "59") (pinfunction "PA.1/QSPI0_MISO0/SPI0_MISO/SC0_DAT/UART0_TXD/UART1_nCTS/PSIO0_CH6/USCI2_DAT0/BPWM0_CH1/PWM0_CH4_59") (pintype "passive"))
    )
    (net (code "79") (name "unconnected-(U2A-PA.2{slash}QSPI0_CLK{slash}SPI0_CLK{slash}SC0_RST{slash}I2C0_SMBSUS{slash}UART1_RXD{slash}I2C1_SDA{slash}PSIO0_CH5{slash}USCI2_CLK{slash}BPWM0_CH2{slash}PWM0_CH3-Pad58)") (class "Default")
      (node (ref "U2") (pin "58") (pinfunction "PA.2/QSPI0_CLK/SPI0_CLK/SC0_RST/I2C0_SMBSUS/UART1_RXD/I2C1_SDA/PSIO0_CH5/USCI2_CLK/BPWM0_CH2/PWM0_CH3_58") (pintype "passive"))
    )
    (net (code "80") (name "unconnected-(U2A-PA.3{slash}QSPI0_SS{slash}SPI0_SS{slash}SC0_PWR{slash}I2C0_SMBAL{slash}UART1_TXD{slash}I2C1_SCL{slash}PSIO0_CH4{slash}USCI2_CTL0{slash}BPWM0_CH3{slash}PWM0_CH2{slash}CLKO{slash}PWM1_BRAKE1-Pad57)") (class "Default")
      (node (ref "U2") (pin "57") (pinfunction "PA.3/QSPI0_SS/SPI0_SS/SC0_PWR/I2C0_SMBAL/UART1_TXD/I2C1_SCL/PSIO0_CH4/USCI2_CTL0/BPWM0_CH3/PWM0_CH2/CLKO/PWM1_BRAKE1_57") (pintype "passive"))
    )
    (net (code "81") (name "unconnected-(U2A-PA.4{slash}QSPI0_MOSI1{slash}SPI0_I2SMCLK{slash}SC0_nCD{slash}UART0_nRTS{slash}UART0_RXD{slash}I2C0_SDA{slash}USCI2_CTL1{slash}BPWM0_CH4{slash}PWM0_CH1-Pad56)") (class "Default")
      (node (ref "U2") (pin "56") (pinfunction "PA.4/QSPI0_MOSI1/SPI0_I2SMCLK/SC0_nCD/UART0_nRTS/UART0_RXD/I2C0_SDA/USCI2_CTL1/BPWM0_CH4/PWM0_CH1_56") (pintype "passive"))
    )
    (net (code "82") (name "unconnected-(U2A-PB.0{slash}EADC0_CH0{slash}OPA0_P{slash}EBI_ADR9{slash}UART2_RXD{slash}SPI0_I2SMCLK{slash}I2C1_SDA{slash}QSPI0_MOSI1{slash}PWM0_CH5{slash}PWM1_CH5{slash}PWM0_BRAKE1-Pad10)") (class "Default")
      (node (ref "U2") (pin "10") (pinfunction "PB.0/EADC0_CH0/OPA0_P/EBI_ADR9/UART2_RXD/SPI0_I2SMCLK/I2C1_SDA/QSPI0_MOSI1/PWM0_CH5/PWM1_CH5/PWM0_BRAKE1_10") (pintype "passive"))
    )
    (net (code "83") (name "unconnected-(U2A-PE.14{slash}EBI_AD8{slash}UART2_TXD{slash}PSIO0_CH0-Pad62)") (class "Default")
      (node (ref "U2") (pin "62") (pinfunction "PE.14/EBI_AD8/UART2_TXD/PSIO0_CH0_62") (pintype "passive"))
    )
    (net (code "84") (name "unconnected-(U2A-PE.15{slash}EBI_AD9{slash}UART2_RXD{slash}PSIO0_CH1-Pad63)") (class "Default")
      (node (ref "U2") (pin "63") (pinfunction "PE.15/EBI_AD9/UART2_RXD/PSIO0_CH1_63") (pintype "passive"))
    )
    (net (code "85") (name "unconnected-(U2B-PB.11{slash}EADC0_CH11{slash}EBI_ADR16{slash}UART0_nCTS{slash}I2C1_SCL{slash}SPI0_I2SMCLK{slash}BPWM1_CH0-Pad123)") (class "Default")
      (node (ref "U2") (pin "123") (pinfunction "PB.11/EADC0_CH11/EBI_ADR16/UART0_nCTS/I2C1_SCL/SPI0_I2SMCLK/BPWM1_CH0_123") (pintype "passive"))
    )
    (net (code "86") (name "unconnected-(U2B-PB.14{slash}EADC0_CH14{slash}EBI_AD13{slash}SPI0_CLK{slash}USCI0_DAT1{slash}UART0_nRTS{slash}PSIO0_CH1{slash}PWM1_CH1{slash}TM1_EXT{slash}CLKO-Pad117)") (class "Default")
      (node (ref "U2") (pin "117") (pinfunction "PB.14/EADC0_CH14/EBI_AD13/SPI0_CLK/USCI0_DAT1/UART0_nRTS/PSIO0_CH1/PWM1_CH1/TM1_EXT/CLKO_117") (pintype "passive"))
    )
    (net (code "87") (name "unconnected-(U2B-PB.15{slash}EADC0_CH15{slash}EBI_AD12{slash}SPI0_SS{slash}USCI0_CTL1{slash}UART0_nCTS{slash}PSIO0_CH0{slash}PWM1_CH0{slash}TM0_EXT{slash}PWM0_BRAKE1-Pad116)") (class "Default")
      (node (ref "U2") (pin "116") (pinfunction "PB.15/EADC0_CH15/EBI_AD12/SPI0_SS/USCI0_CTL1/UART0_nCTS/PSIO0_CH0/PWM1_CH0/TM0_EXT/PWM0_BRAKE1_116") (pintype "passive"))
    )
    (net (code "88") (name "unconnected-(U2B-PC.14{slash}EBI_AD11{slash}SPI0_I2SMCLK{slash}USCI0_CTL0{slash}QSPI0_CLK{slash}USCI2_CLK{slash}TM1-Pad115)") (class "Default")
      (node (ref "U2") (pin "115") (pinfunction "PC.14/EBI_AD11/SPI0_I2SMCLK/USCI0_CTL0/QSPI0_CLK/USCI2_CLK/TM1_115") (pintype "passive"))
    )
    (net (code "89") (name "unconnected-(U2B-PD.5{slash}I2C1_SCL{slash}USCI1_DAT0{slash}PSIO0_CH6-Pad86)") (class "Default")
      (node (ref "U2") (pin "86") (pinfunction "PD.5/I2C1_SCL/USCI1_DAT0/PSIO0_CH6_86") (pintype "passive"))
    )
    (net (code "90") (name "unconnected-(U2B-PD.6{slash}UART1_RXD{slash}I2C0_SDA{slash}USCI1_DAT1{slash}PSIO0_CH5-Pad85)") (class "Default")
      (node (ref "U2") (pin "85") (pinfunction "PD.6/UART1_RXD/I2C0_SDA/USCI1_DAT1/PSIO0_CH5_85") (pintype "passive"))
    )
    (net (code "91") (name "unconnected-(U2B-PD.7{slash}UART1_TXD{slash}I2C0_SCL{slash}USCI1_CLK{slash}PSIO0_CH4-Pad84)") (class "Default")
      (node (ref "U2") (pin "84") (pinfunction "PD.7/UART1_TXD/I2C0_SCL/USCI1_CLK/PSIO0_CH4_84") (pintype "passive"))
    )
    (net (code "92") (name "unconnected-(U2B-PD.8{slash}EBI_AD6{slash}UART2_nRTS{slash}PSIO0_CH3-Pad68)") (class "Default")
      (node (ref "U2") (pin "68") (pinfunction "PD.8/EBI_AD6/UART2_nRTS/PSIO0_CH3_68") (pintype "passive"))
    )
    (net (code "93") (name "unconnected-(U2B-PE.3{slash}EBI_MCLK{slash}SC0_DAT{slash}USCI0_DAT0{slash}PWM0_CH4{slash}BPWM0_CH1-Pad101)") (class "Default")
      (node (ref "U2") (pin "101") (pinfunction "PE.3/EBI_MCLK/SC0_DAT/USCI0_DAT0/PWM0_CH4/BPWM0_CH1_101") (pintype "passive"))
    )
    (net (code "94") (name "unconnected-(U2B-PE.4{slash}EBI_nWR{slash}SC0_RST{slash}USCI0_DAT1{slash}PSIO0_CH3{slash}PWM0_CH3{slash}BPWM0_CH2-Pad100)") (class "Default")
      (node (ref "U2") (pin "100") (pinfunction "PE.4/EBI_nWR/SC0_RST/USCI0_DAT1/PSIO0_CH3/PWM0_CH3/BPWM0_CH2_100") (pintype "passive"))
    )
    (net (code "95") (name "unconnected-(U2B-PE.5{slash}EBI_nRD{slash}SC0_PWR{slash}USCI0_CTL1{slash}PSIO0_CH2{slash}PWM0_CH2{slash}BPWM0_CH3-Pad99)") (class "Default")
      (node (ref "U2") (pin "99") (pinfunction "PE.5/EBI_nRD/SC0_PWR/USCI0_CTL1/PSIO0_CH2/PWM0_CH2/BPWM0_CH3_99") (pintype "passive"))
    )
    (net (code "96") (name "unconnected-(U2B-PE.6{slash}SC0_nCD{slash}USCI0_CTL0{slash}PSIO0_CH1{slash}PWM0_CH1{slash}BPWM0_CH4-Pad98)") (class "Default")
      (node (ref "U2") (pin "98") (pinfunction "PE.6/SC0_nCD/USCI0_CTL0/PSIO0_CH1/PWM0_CH1/BPWM0_CH4_98") (pintype "passive"))
    )
    (net (code "97") (name "unconnected-(U2B-PE.7{slash}PSIO0_CH0{slash}PWM0_CH0{slash}BPWM0_CH5-Pad97)") (class "Default")
      (node (ref "U2") (pin "97") (pinfunction "PE.7/PSIO0_CH0/PWM0_CH0/BPWM0_CH5_97") (pintype "passive"))
    )
  )
)
